# HW1_Witt_u1090350.net
KiCad netlist of a schematic drawn in Altium Designer
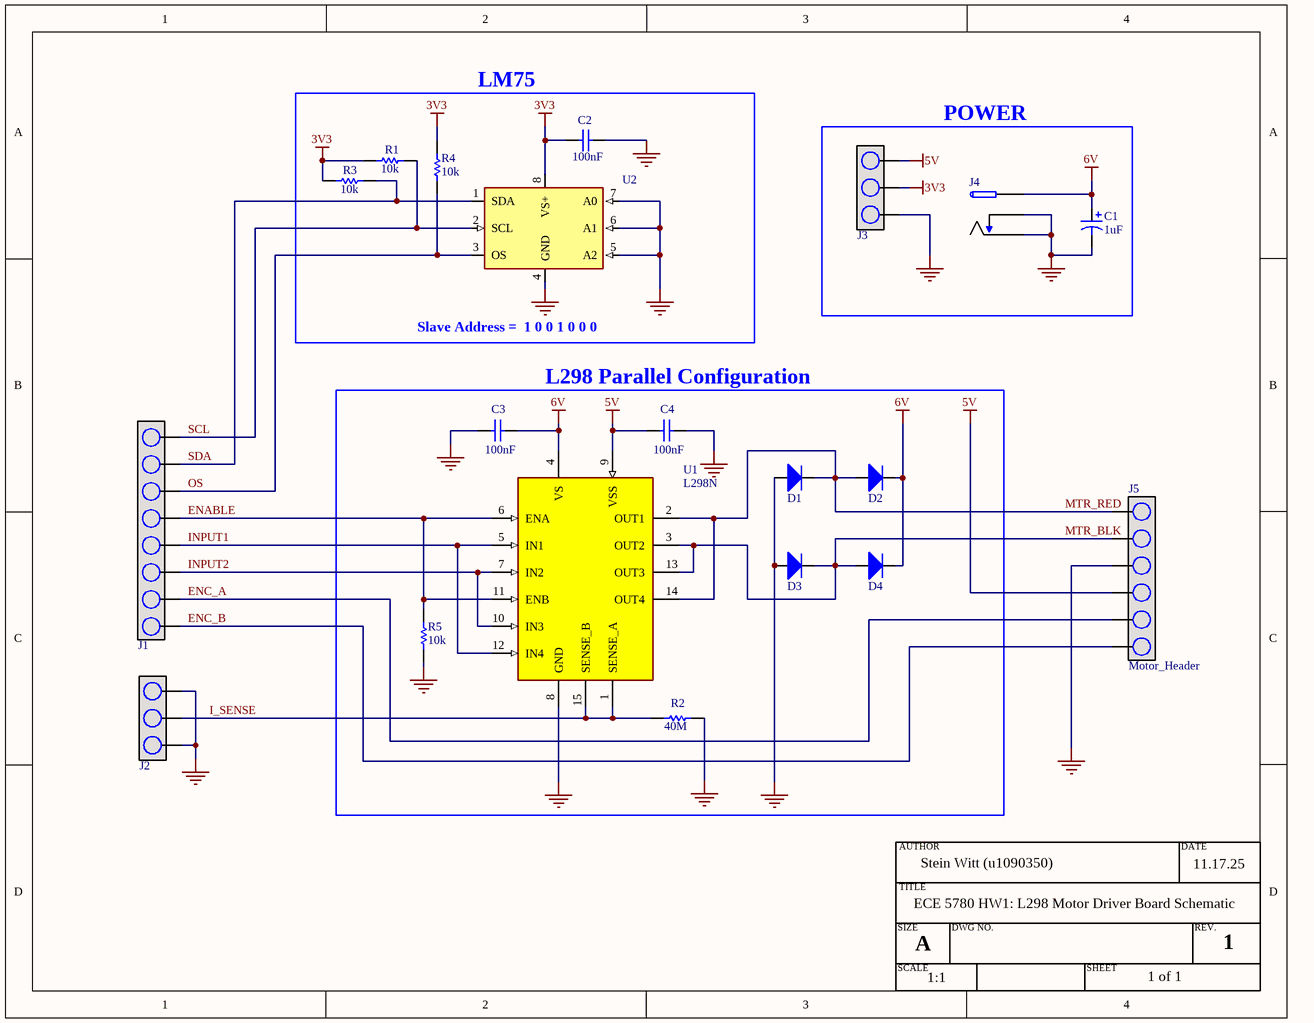
[diagram p0: HW1_Witt_u1090350.SchDoc]

(export (version "E")
  (design (tool "Eeschema 10.0.6"))
  (components
    (comp (ref "*") (value "Title Block") (libsource (lib "LM298_Schematic_Library") (part "Title Block")))
    (comp (ref "C1")
      (value "1uF")
      (footprint "CAP_TH_Radial_0511")
      (description "Radial Leaded 160V 1.0uF 20% 5x11mm")
      (fields
        (field (name "MANUFACTURER") "Lelon")
        (field (name "MANUFACTURER PART NUMBER") "REA010M2CBK-0511P")
      )
      (libsource (lib "LM298_Schematic_Library") (part "REA010M2CBK-0511P"))
    )
    (comp (ref "C2")
      (value "C1206C104K5RAC7800")
      (footprint "CAP_1206")
      (description "0.1 µF ±10% 50V Ceramic Capacitor X7R 1206 (3216 Metric)")
      (fields (field (name "CAPACITANCE") "100nF"))
      (libsource (lib "LM298_Schematic_Library") (part "C1206C104K5RAC7800"))
    )
    (comp (ref "C3")
      (value "C1206C104K5RAC7800")
      (footprint "CAP_1206")
      (description "0.1 µF ±10% 50V Ceramic Capacitor X7R 1206 (3216 Metric)")
      (fields (field (name "CAPACITANCE") "100nF"))
      (libsource (lib "LM298_Schematic_Library") (part "C1206C104K5RAC7800"))
    )
    (comp (ref "C4")
      (value "C1206C104K5RAC7800")
      (footprint "CAP_1206")
      (description "0.1 µF ±10% 50V Ceramic Capacitor X7R 1206 (3216 Metric)")
      (fields (field (name "CAPACITANCE") "100nF"))
      (libsource (lib "LM298_Schematic_Library") (part "C1206C104K5RAC7800"))
    )
    (comp (ref "D1")
      (value "RS2AA R3G")
      (footprint "RS2AA")
      (description "Diode Fast Recovery Rectifier 50V 1.5A 2-Pin DO-214AC Plastic T/R")
      (fields (field (name "MANUFACTURER") "Taiwan Semiconductor"))
      (libsource (lib "LM298_Schematic_Library") (part "RS2AA R3G"))
    )
    (comp (ref "D2")
      (value "RS2AA R3G")
      (footprint "RS2AA")
      (description "Diode Fast Recovery Rectifier 50V 1.5A 2-Pin DO-214AC Plastic T/R")
      (fields (field (name "MANUFACTURER") "Taiwan Semiconductor"))
      (libsource (lib "LM298_Schematic_Library") (part "RS2AA R3G"))
    )
    (comp (ref "D3")
      (value "RS2AA R3G")
      (footprint "RS2AA")
      (description "Diode Fast Recovery Rectifier 50V 1.5A 2-Pin DO-214AC Plastic T/R")
      (fields (field (name "MANUFACTURER") "Taiwan Semiconductor"))
      (libsource (lib "LM298_Schematic_Library") (part "RS2AA R3G"))
    )
    (comp (ref "D4")
      (value "RS2AA R3G")
      (footprint "RS2AA")
      (description "Diode Fast Recovery Rectifier 50V 1.5A 2-Pin DO-214AC Plastic T/R")
      (fields (field (name "MANUFACTURER") "Taiwan Semiconductor"))
      (libsource (lib "LM298_Schematic_Library") (part "RS2AA R3G"))
    )
    (comp (ref "J1")
      (value "8 Pin Male Connector")
      (footprint "8 Pin THT Header")
      (libsource (lib "LM298_Schematic_Library") (part "8 Pin Male Connector"))
    )
    (comp (ref "J2")
      (value "3 Pin 2.54mm Male Connector")
      (footprint "3 Pin THT Header")
      (libsource (lib "LM298_Schematic_Library") (part "3 Pin 2.54mm Male Connector"))
    )
    (comp (ref "J3")
      (value "3 Pin 2.54mm Male Connector")
      (footprint "3 Pin THT Header")
      (libsource (lib "LM298_Schematic_Library") (part "3 Pin 2.54mm Male Connector"))
    )
    (comp (ref "J4")
      (value "Barrel Jack")
      (footprint "GRAVITECH_CON-SOCJ-2155")
      (libsource (lib "LM298_Schematic_Library") (part "Barrel Jack"))
    )
    (comp (ref "J5")
      (value "Motor_Header")
      (footprint "6 Pin THT Header")
      (libsource (lib "LM298_Schematic_Library") (part "6 pin 2.54mm Male Connector"))
    )
    (comp (ref "R1")
      (value "10k")
      (footprint "RES_1206")
      (description "Res Thick Film 1206 10K Ohm 5% 1/4W ¦100ppm/¦C SMD Paper T/R")
      (fields
        (field (name "MANUFACTURER") "Yageo")
        (field (name "MANUFACTURER PART NUMBER") "RC1206JR-0710KL")
      )
      (libsource (lib "LM298_Schematic_Library") (part "RC1206JR-0710KL"))
    )
    (comp (ref "R2")
      (value "40M")
      (footprint "RES_1206")
      (description "SMD Current Sense Resistor, 40 Milliohms, ± 1%, 250 mW, 1206 [3216 Metric], Thick Film")
      (fields
        (field (name "MANUFACTURER") "Yageo")
        (field (name "MANUFACTURER PART NUMBER") "RL1206FR-070R04L")
      )
      (libsource (lib "LM298_Schematic_Library") (part "RL1206FR-070R04L"))
    )
    (comp (ref "R3")
      (value "10k")
      (footprint "RES_1206")
      (description "Res Thick Film 1206 10K Ohm 5% 1/4W ¦100ppm/¦C SMD Paper T/R")
      (fields
        (field (name "MANUFACTURER") "Yageo")
        (field (name "MANUFACTURER PART NUMBER") "RC1206JR-0710KL")
      )
      (libsource (lib "LM298_Schematic_Library") (part "RC1206JR-0710KL"))
    )
    (comp (ref "R4")
      (value "10k")
      (footprint "RES_1206")
      (description "Res Thick Film 1206 10K Ohm 5% 1/4W ¦100ppm/¦C SMD Paper T/R")
      (fields
        (field (name "MANUFACTURER") "Yageo")
        (field (name "MANUFACTURER PART NUMBER") "RC1206JR-0710KL")
      )
      (libsource (lib "LM298_Schematic_Library") (part "RC1206JR-0710KL"))
    )
    (comp (ref "R5")
      (value "10k")
      (footprint "RES_1206")
      (description "Res Thick Film 1206 10K Ohm 5% 1/4W ¦100ppm/¦C SMD Paper T/R")
      (fields
        (field (name "MANUFACTURER") "Yageo")
        (field (name "MANUFACTURER PART NUMBER") "RC1206JR-0710KL")
      )
      (libsource (lib "LM298_Schematic_Library") (part "RC1206JR-0710KL"))
    )
    (comp (ref "U1")
      (value "L298N")
      (footprint "L298N")
      (description "Dual Full Bridge Motor Driver 15-Pin(15+Tab) MULTIWATT V Tube")
      (libsource (lib "LM298_Schematic_Library") (part "L298N"))
    )
    (comp (ref "U2")
      (value "LM75AIMXNOPB")
      (footprint "SOIC8")
      (description "No Description Available")
      (libsource (lib "LM298_Schematic_Library") (part "LM75AIMXNOPB"))
    )
  )
  (nets
    (net (code "1") (name "/ENABLE") (class "Default")
      (node (ref "J1") (pin "5") (pinfunction "5_5") (pintype "passive"))
      (node (ref "R5") (pin "2") (pinfunction "2_2") (pintype "passive"))
      (node (ref "U1") (pin "11") (pinfunction "ENB_11") (pintype "input"))
      (node (ref "U1") (pin "6") (pinfunction "ENA_6") (pintype "input"))
    )
    (net (code "2") (name "/ENC_A") (class "Default")
      (node (ref "J1") (pin "2") (pinfunction "2_2") (pintype "passive"))
      (node (ref "J5") (pin "5") (pinfunction "5_5") (pintype "passive"))
    )
    (net (code "3") (name "/ENC_B") (class "Default")
      (node (ref "J1") (pin "1") (pinfunction "1_1") (pintype "passive"))
      (node (ref "J5") (pin "6") (pinfunction "6_6") (pintype "passive"))
    )
    (net (code "4") (name "/INPUT1") (class "Default")
      (node (ref "J1") (pin "4") (pinfunction "4_4") (pintype "passive"))
      (node (ref "U1") (pin "12") (pinfunction "IN4_12") (pintype "input"))
      (node (ref "U1") (pin "5") (pinfunction "IN1_5") (pintype "input"))
    )
    (net (code "5") (name "/INPUT2") (class "Default")
      (node (ref "J1") (pin "3") (pinfunction "3_3") (pintype "passive"))
      (node (ref "U1") (pin "10") (pinfunction "IN3_10") (pintype "input"))
      (node (ref "U1") (pin "7") (pinfunction "IN2_7") (pintype "input"))
    )
    (net (code "6") (name "/I_SENSE") (class "Default")
      (node (ref "J2") (pin "2") (pinfunction "2_2") (pintype "passive"))
      (node (ref "R2") (pin "2") (pinfunction "2_2") (pintype "passive"))
      (node (ref "U1") (pin "1") (pinfunction "SENSE_A_1") (pintype "passive"))
      (node (ref "U1") (pin "15") (pinfunction "SENSE_B_15") (pintype "passive"))
    )
    (net (code "7") (name "/MTR_BLK") (class "Default")
      (node (ref "D3") (pin "1") (pinfunction "K_1") (pintype "passive"))
      (node (ref "D4") (pin "2") (pinfunction "A_2") (pintype "passive"))
      (node (ref "J5") (pin "2") (pinfunction "2_2") (pintype "passive"))
      (node (ref "U1") (pin "13") (pinfunction "OUT3_13") (pintype "open_collector"))
      (node (ref "U1") (pin "3") (pinfunction "OUT2_3") (pintype "passive"))
    )
    (net (code "8") (name "/MTR_RED") (class "Default")
      (node (ref "D1") (pin "1") (pinfunction "K_1") (pintype "passive"))
      (node (ref "D2") (pin "2") (pinfunction "A_2") (pintype "passive"))
      (node (ref "J5") (pin "1") (pinfunction "1_1") (pintype "passive"))
      (node (ref "U1") (pin "14") (pinfunction "OUT4_14") (pintype "passive"))
      (node (ref "U1") (pin "2") (pinfunction "OUT1_2") (pintype "passive"))
    )
    (net (code "9") (name "/OS") (class "Default")
      (node (ref "J1") (pin "6") (pinfunction "6_6") (pintype "passive"))
      (node (ref "R4") (pin "1") (pinfunction "1_1") (pintype "passive"))
      (node (ref "U2") (pin "3") (pinfunction "OS_3") (pintype "passive"))
    )
    (net (code "10") (name "/SCL") (class "Default")
      (node (ref "J1") (pin "8") (pinfunction "8_8") (pintype "passive"))
      (node (ref "R1") (pin "2") (pinfunction "2_2") (pintype "passive"))
      (node (ref "U2") (pin "2") (pinfunction "SCL_2") (pintype "input"))
    )
    (net (code "11") (name "/SDA") (class "Default")
      (node (ref "J1") (pin "7") (pinfunction "7_7") (pintype "passive"))
      (node (ref "R3") (pin "2") (pinfunction "2_2") (pintype "passive"))
      (node (ref "U2") (pin "1") (pinfunction "SDA_1") (pintype "bidirectional"))
    )
    (net (code "12") (name "3V3") (class "Default")
      (node (ref "C2") (pin "2") (pinfunction "2_2") (pintype "passive"))
      (node (ref "J3") (pin "2") (pinfunction "2_2") (pintype "passive"))
      (node (ref "R1") (pin "1") (pinfunction "1_1") (pintype "passive"))
      (node (ref "R3") (pin "1") (pinfunction "1_1") (pintype "passive"))
      (node (ref "R4") (pin "2") (pinfunction "2_2") (pintype "passive"))
      (node (ref "U2") (pin "8") (pinfunction "VS+_8") (pintype "power_in"))
    )
    (net (code "13") (name "5V") (class "Default")
      (node (ref "C4") (pin "1") (pinfunction "1_1") (pintype "passive"))
      (node (ref "J3") (pin "3") (pinfunction "3_3") (pintype "passive"))
      (node (ref "J5") (pin "4") (pinfunction "4_4") (pintype "passive"))
      (node (ref "U1") (pin "9") (pinfunction "VSS_9") (pintype "input"))
    )
    (net (code "14") (name "6V") (class "Default")
      (node (ref "C1") (pin "2") (pinfunction "+_2") (pintype "passive"))
      (node (ref "C3") (pin "2") (pinfunction "2_2") (pintype "passive"))
      (node (ref "D2") (pin "1") (pinfunction "K_1") (pintype "passive"))
      (node (ref "D4") (pin "1") (pinfunction "K_1") (pintype "passive"))
      (node (ref "J4") (pin "1") (pinfunction "POS_1") (pintype "passive"))
      (node (ref "U1") (pin "4") (pinfunction "VS_4") (pintype "power_in"))
    )
    (net (code "15") (name "GND") (class "Default")
      (node (ref "C1") (pin "1") (pinfunction "-_1") (pintype "passive"))
      (node (ref "C2") (pin "1") (pinfunction "1_1") (pintype "passive"))
      (node (ref "C3") (pin "1") (pinfunction "1_1") (pintype "passive"))
      (node (ref "C4") (pin "2") (pinfunction "2_2") (pintype "passive"))
      (node (ref "D1") (pin "2") (pinfunction "A_2") (pintype "passive"))
      (node (ref "D3") (pin "2") (pinfunction "A_2") (pintype "passive"))
      (node (ref "J2") (pin "1") (pinfunction "1_1") (pintype "passive"))
      (node (ref "J2") (pin "3") (pinfunction "3_3") (pintype "passive"))
      (node (ref "J3") (pin "1") (pinfunction "1_1") (pintype "passive"))
      (node (ref "J4") (pin "2") (pinfunction "NEG_2") (pintype "passive"))
      (node (ref "J4") (pin "3") (pinfunction "SW_3") (pintype "passive"))
      (node (ref "J5") (pin "3") (pinfunction "3_3") (pintype "passive"))
      (node (ref "R2") (pin "1") (pinfunction "1_1") (pintype "passive"))
      (node (ref "R5") (pin "1") (pinfunction "1_1") (pintype "passive"))
      (node (ref "U1") (pin "8") (pinfunction "GND_8") (pintype "power_in"))
      (node (ref "U2") (pin "4") (pinfunction "GND_4") (pintype "power_in"))
      (node (ref "U2") (pin "5") (pinfunction "A2_5") (pintype "input"))
      (node (ref "U2") (pin "6") (pinfunction "A1_6") (pintype "input"))
      (node (ref "U2") (pin "7") (pinfunction "A0_7") (pintype "input"))
    )
  )
)
